# Stoitsov_Bostandzhieva.net
KiCad netlist of a schematic drawn in EAGLE
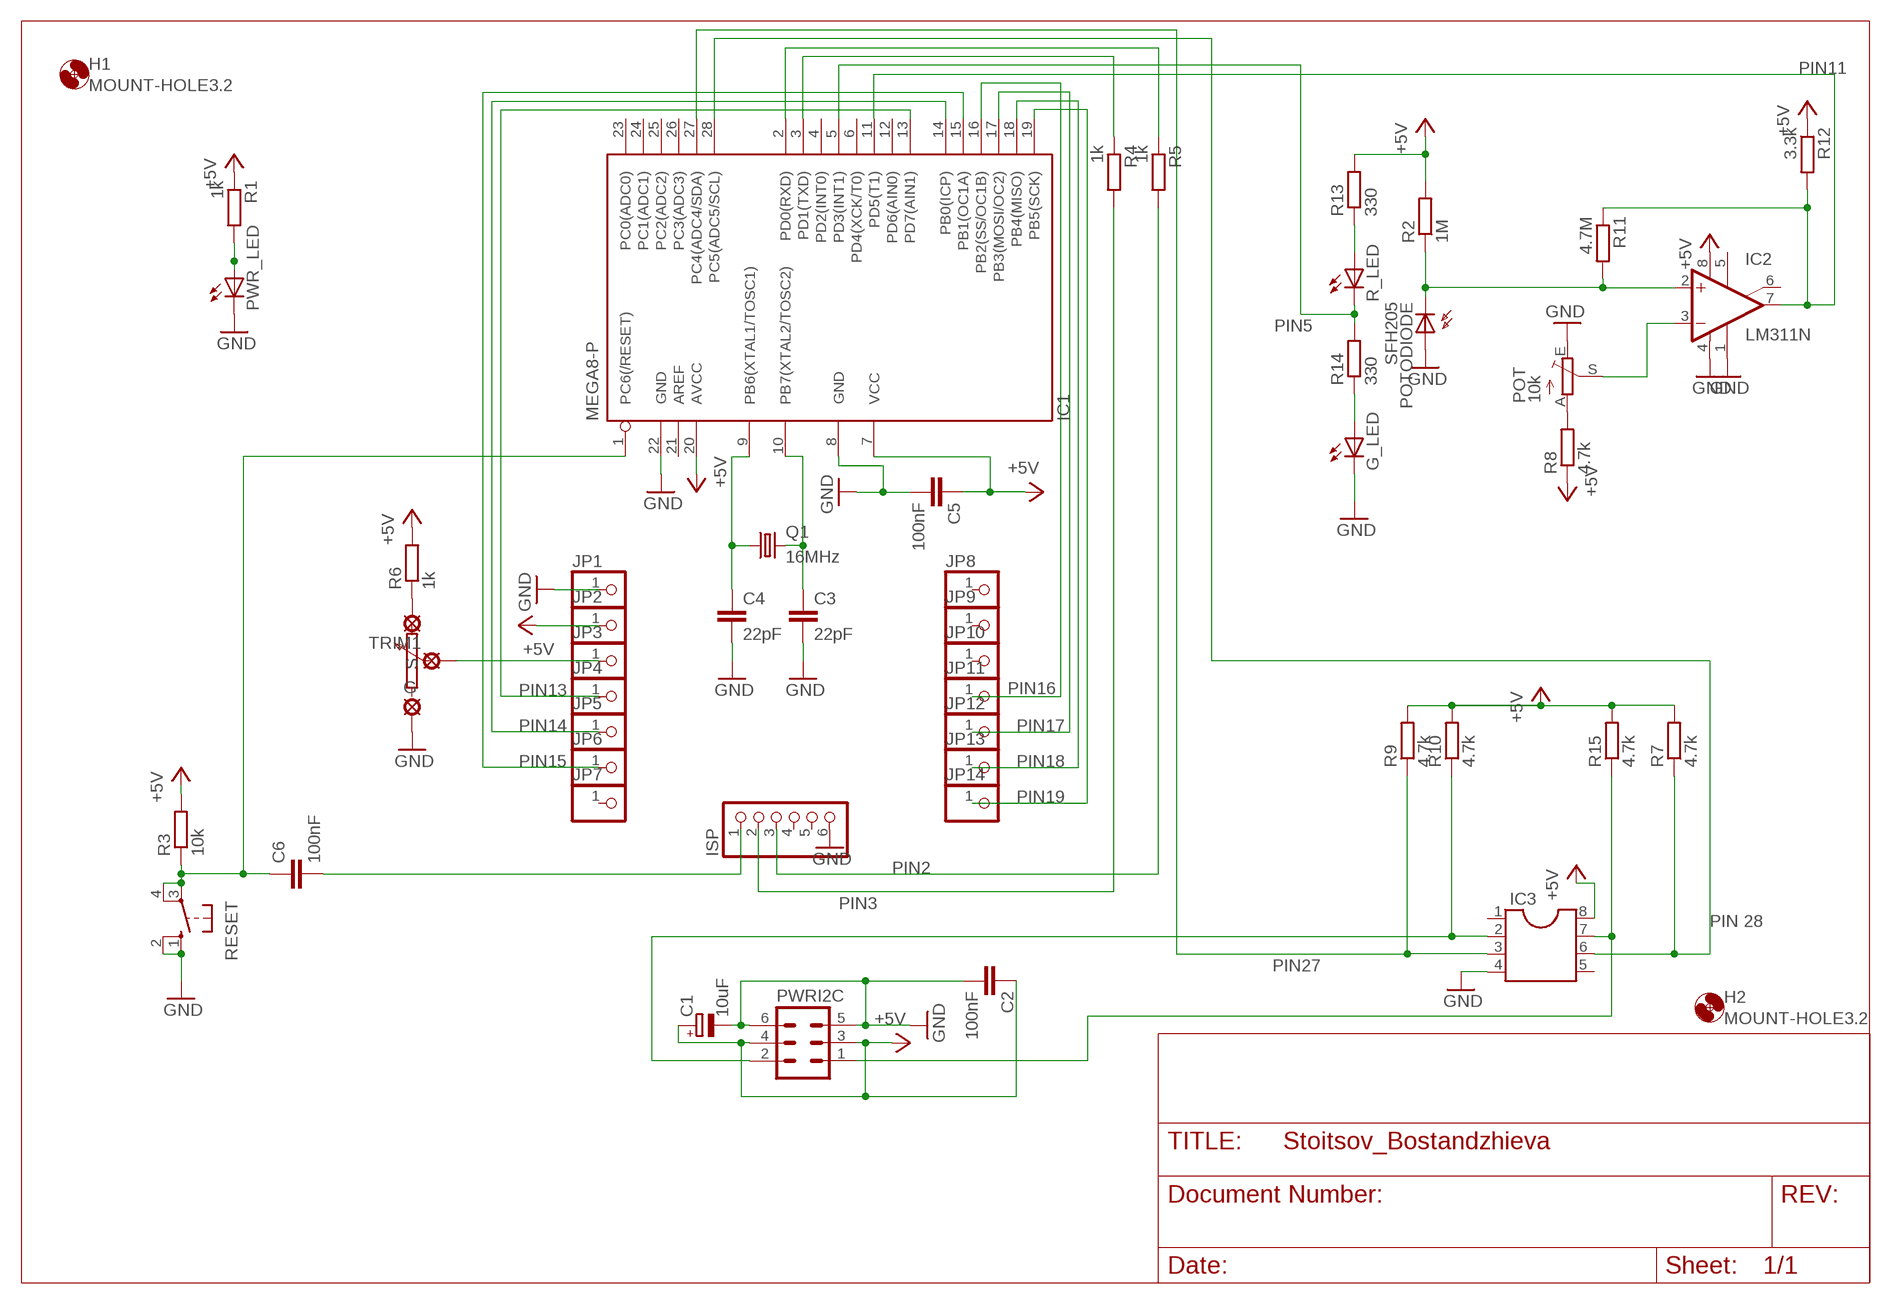
[diagram p0: schematic, sheet 1]

(export (version "E")
  (design (tool "Eeschema 10.0.6"))
  (components
    (comp (ref "C1")
      (value "10uF")
      (footprint "eagle-import:E5-6")
      (libsource (lib "eagle-import") (part "CPOL-EUE5-6"))
    )
    (comp (ref "C2")
      (value "100nF")
      (footprint "eagle-import:C5B2.5")
      (libsource (lib "eagle-import") (part "C5/2.5"))
    )
    (comp (ref "C3")
      (value "22pF")
      (footprint "eagle-import:C5B2.5")
      (libsource (lib "eagle-import") (part "C5/2.5"))
    )
    (comp (ref "C4")
      (value "22pF")
      (footprint "eagle-import:C5B2.5")
      (libsource (lib "eagle-import") (part "C5/2.5"))
    )
    (comp (ref "C5")
      (value "100nF")
      (footprint "eagle-import:C5B2.5")
      (libsource (lib "eagle-import") (part "C5/2.5"))
    )
    (comp (ref "C6")
      (value "100nF")
      (footprint "eagle-import:C5B2.5")
      (libsource (lib "eagle-import") (part "C5/2.5"))
    )
    (comp (ref "G")
      (value "LSP11")
      (footprint "eagle-import:LSP11")
      (libsource (lib "eagle-import") (part "LSP11"))
    )
    (comp (ref "G_LED")
      (value "LED3MM")
      (footprint "eagle-import:LED3MM")
      (libsource (lib "eagle-import") (part "LED3MM"))
    )
    (comp (ref "H1")
      (value "MOUNT-HOLE3.2")
      (footprint "eagle-import:3,2")
      (libsource (lib "eagle-import") (part "MOUNT-HOLE3.2"))
    )
    (comp (ref "H2")
      (value "MOUNT-HOLE3.2")
      (footprint "eagle-import:3,2")
      (libsource (lib "eagle-import") (part "MOUNT-HOLE3.2"))
    )
    (comp (ref "IC1")
      (value "MEGA8-P")
      (footprint "eagle-import:DIL28-3")
      (libsource (lib "eagle-import") (part "MEGA8-P"))
    )
    (comp (ref "IC2")
      (value "LM311N")
      (footprint "eagle-import:DIL08")
      (libsource (lib "eagle-import") (part "LM311N"))
    )
    (comp (ref "IC3")
      (value "DIL8S")
      (footprint "eagle-import:SOCKET-08")
      (libsource (lib "eagle-import") (part "DIL8S"))
    )
    (comp (ref "ISP")
      (value "PINHD-1X6/90")
      (footprint "eagle-import:1X06_90")
      (libsource (lib "eagle-import") (part "PINHD-1X6/90"))
    )
    (comp (ref "JP1")
      (value "PINHD-1X1")
      (footprint "eagle-import:1X01")
      (libsource (lib "eagle-import") (part "PINHD-1X1"))
    )
    (comp (ref "JP2")
      (value "PINHD-1X1")
      (footprint "eagle-import:1X01")
      (libsource (lib "eagle-import") (part "PINHD-1X1"))
    )
    (comp (ref "JP3")
      (value "PINHD-1X1")
      (footprint "eagle-import:1X01")
      (libsource (lib "eagle-import") (part "PINHD-1X1"))
    )
    (comp (ref "JP4")
      (value "PINHD-1X1")
      (footprint "eagle-import:1X01")
      (libsource (lib "eagle-import") (part "PINHD-1X1"))
    )
    (comp (ref "JP5")
      (value "PINHD-1X1")
      (footprint "eagle-import:1X01")
      (libsource (lib "eagle-import") (part "PINHD-1X1"))
    )
    (comp (ref "JP6")
      (value "PINHD-1X1")
      (footprint "eagle-import:1X01")
      (libsource (lib "eagle-import") (part "PINHD-1X1"))
    )
    (comp (ref "JP7")
      (value "PINHD-1X1")
      (footprint "eagle-import:1X01")
      (libsource (lib "eagle-import") (part "PINHD-1X1"))
    )
    (comp (ref "JP8")
      (value "PINHD-1X1")
      (footprint "eagle-import:1X01")
      (libsource (lib "eagle-import") (part "PINHD-1X1"))
    )
    (comp (ref "JP9")
      (value "PINHD-1X1")
      (footprint "eagle-import:1X01")
      (libsource (lib "eagle-import") (part "PINHD-1X1"))
    )
    (comp (ref "JP10")
      (value "PINHD-1X1")
      (footprint "eagle-import:1X01")
      (libsource (lib "eagle-import") (part "PINHD-1X1"))
    )
    (comp (ref "JP11")
      (value "PINHD-1X1")
      (footprint "eagle-import:1X01")
      (libsource (lib "eagle-import") (part "PINHD-1X1"))
    )
    (comp (ref "JP12")
      (value "PINHD-1X1")
      (footprint "eagle-import:1X01")
      (libsource (lib "eagle-import") (part "PINHD-1X1"))
    )
    (comp (ref "JP13")
      (value "PINHD-1X1")
      (footprint "eagle-import:1X01")
      (libsource (lib "eagle-import") (part "PINHD-1X1"))
    )
    (comp (ref "JP14")
      (value "PINHD-1X1")
      (footprint "eagle-import:1X01")
      (libsource (lib "eagle-import") (part "PINHD-1X1"))
    )
    (comp (ref "POT")
      (value "10k")
      (footprint "eagle-import:S64W")
      (libsource (lib "eagle-import") (part "TRIM_EU-S64W"))
    )
    (comp (ref "POTODIODE")
      (value "SFH205")
      (footprint "eagle-import:SFH205")
      (libsource (lib "eagle-import") (part "SFH205"))
    )
    (comp (ref "PWRI2C")
      (value "MA03-2")
      (footprint "eagle-import:MA03-2")
      (libsource (lib "eagle-import") (part "MA03-2"))
    )
    (comp (ref "PWR_LED")
      (value "LED3MM")
      (footprint "eagle-import:LED3MM")
      (libsource (lib "eagle-import") (part "LED3MM"))
    )
    (comp (ref "Q1")
      (value "16MHz")
      (footprint "eagle-import:HC18U-V")
      (libsource (lib "eagle-import") (part "CRYSTALHC18U-V"))
    )
    (comp (ref "R1")
      (value "1k")
      (footprint "eagle-import:0207_12")
      (libsource (lib "eagle-import") (part "R-EU_0207/12"))
    )
    (comp (ref "R2")
      (value "1M")
      (footprint "eagle-import:0207_12")
      (libsource (lib "eagle-import") (part "R-EU_0207/12"))
    )
    (comp (ref "R3")
      (value "10k")
      (footprint "eagle-import:0207_12")
      (libsource (lib "eagle-import") (part "R-EU_0207/12"))
    )
    (comp (ref "R4")
      (value "1k")
      (footprint "eagle-import:0207_12")
      (libsource (lib "eagle-import") (part "R-EU_0207/12"))
    )
    (comp (ref "R5")
      (value "1k")
      (footprint "eagle-import:0207_12")
      (libsource (lib "eagle-import") (part "R-EU_0207/12"))
    )
    (comp (ref "R6")
      (value "1k")
      (footprint "eagle-import:0207_12")
      (libsource (lib "eagle-import") (part "R-EU_0207/12"))
    )
    (comp (ref "R7")
      (value "4.7k")
      (footprint "eagle-import:0207_12")
      (libsource (lib "eagle-import") (part "R-EU_0207/12"))
    )
    (comp (ref "R8")
      (value "4.7k")
      (footprint "eagle-import:0207_12")
      (libsource (lib "eagle-import") (part "R-EU_0207/12"))
    )
    (comp (ref "R9")
      (value "4.7k")
      (footprint "eagle-import:0207_12")
      (libsource (lib "eagle-import") (part "R-EU_0207/12"))
    )
    (comp (ref "R10")
      (value "4.7k")
      (footprint "eagle-import:0207_12")
      (libsource (lib "eagle-import") (part "R-EU_0207/12"))
    )
    (comp (ref "R11")
      (value "4.7M")
      (footprint "eagle-import:0207_12")
      (libsource (lib "eagle-import") (part "R-EU_0207/12"))
    )
    (comp (ref "R12")
      (value "3.3k")
      (footprint "eagle-import:0207_12")
      (libsource (lib "eagle-import") (part "R-EU_0207/12"))
    )
    (comp (ref "R13")
      (value "330")
      (footprint "eagle-import:0207_12")
      (libsource (lib "eagle-import") (part "R-EU_0207/12"))
    )
    (comp (ref "R14")
      (value "330")
      (footprint "eagle-import:0207_12")
      (libsource (lib "eagle-import") (part "R-EU_0207/12"))
    )
    (comp (ref "R15")
      (value "4.7k")
      (footprint "eagle-import:0207_12")
      (libsource (lib "eagle-import") (part "R-EU_0207/12"))
    )
    (comp (ref "RESET")
      (value "10-XX")
      (footprint "eagle-import:B3F-10XX")
      (fields (field (name "MPN") "B3F-1000"))
      (libsource (lib "eagle-import") (part "10-XX"))
    )
    (comp (ref "R_LED")
      (value "LED3MM")
      (footprint "eagle-import:LED3MM")
      (libsource (lib "eagle-import") (part "LED3MM"))
    )
    (comp (ref "S")
      (value "LSP11")
      (footprint "eagle-import:LSP11")
      (libsource (lib "eagle-import") (part "LSP11"))
    )
    (comp (ref "TRIM1")
      (value "LSP11")
      (footprint "eagle-import:LSP11")
      (libsource (lib "eagle-import") (part "LSP11"))
    )
  )
  (nets
    (net (code "1") (name "+5V") (class "Default")
      (node (ref "C1") (pin "+") (pinfunction "+_+") (pintype "passive"))
      (node (ref "C2") (pin "1") (pinfunction "1_1") (pintype "passive"))
      (node (ref "C5") (pin "1") (pinfunction "1_1") (pintype "passive"))
      (node (ref "IC1") (pin "20") (pinfunction "AVCC_20") (pintype "power_in"))
      (node (ref "IC1") (pin "7") (pinfunction "VCC_7") (pintype "power_in"))
      (node (ref "IC2") (pin "8") (pinfunction "V+_8") (pintype "power_in"))
      (node (ref "IC3") (pin "8") (pinfunction "8_8") (pintype "passive"))
      (node (ref "JP2") (pin "1") (pinfunction "1_1") (pintype "passive"))
      (node (ref "PWRI2C") (pin "3") (pinfunction "3_3") (pintype "passive"))
      (node (ref "PWRI2C") (pin "4") (pinfunction "4_4") (pintype "passive"))
      (node (ref "R1") (pin "1") (pinfunction "1_1") (pintype "passive"))
      (node (ref "R10") (pin "2") (pinfunction "2_2") (pintype "passive"))
      (node (ref "R12") (pin "1") (pinfunction "1_1") (pintype "passive"))
      (node (ref "R13") (pin "2") (pinfunction "2_2") (pintype "passive"))
      (node (ref "R15") (pin "2") (pinfunction "2_2") (pintype "passive"))
      (node (ref "R2") (pin "2") (pinfunction "2_2") (pintype "passive"))
      (node (ref "R3") (pin "2") (pinfunction "2_2") (pintype "passive"))
      (node (ref "R6") (pin "2") (pinfunction "2_2") (pintype "passive"))
      (node (ref "R7") (pin "2") (pinfunction "2_2") (pintype "passive"))
      (node (ref "R8") (pin "1") (pinfunction "1_1") (pintype "passive"))
      (node (ref "R9") (pin "2") (pinfunction "2_2") (pintype "passive"))
    )
    (net (code "2") (name "GND") (class "Default")
      (node (ref "C1") (pin "-") (pinfunction "-_-") (pintype "passive"))
      (node (ref "C2") (pin "2") (pinfunction "2_2") (pintype "passive"))
      (node (ref "C3") (pin "2") (pinfunction "2_2") (pintype "passive"))
      (node (ref "C4") (pin "2") (pinfunction "2_2") (pintype "passive"))
      (node (ref "C5") (pin "2") (pinfunction "2_2") (pintype "passive"))
      (node (ref "G") (pin "MP") (pinfunction "MP_MP") (pintype "passive"))
      (node (ref "G_LED") (pin "K") (pinfunction "C_K") (pintype "passive"))
      (node (ref "IC1") (pin "22") (pinfunction "GND_22") (pintype "power_in"))
      (node (ref "IC1") (pin "8") (pinfunction "GND_8") (pintype "power_in"))
      (node (ref "IC2") (pin "1") (pinfunction "GND_1") (pintype "passive"))
      (node (ref "IC2") (pin "4") (pinfunction "V-_4") (pintype "power_in"))
      (node (ref "IC3") (pin "4") (pinfunction "4_4") (pintype "passive"))
      (node (ref "ISP") (pin "6") (pinfunction "6_6") (pintype "passive"))
      (node (ref "JP1") (pin "1") (pinfunction "1_1") (pintype "passive"))
      (node (ref "POT") (pin "E") (pinfunction "E_E") (pintype "passive"))
      (node (ref "POTODIODE") (pin "A") (pinfunction "A_A") (pintype "passive"))
      (node (ref "PWRI2C") (pin "5") (pinfunction "5_5") (pintype "passive"))
      (node (ref "PWRI2C") (pin "6") (pinfunction "6_6") (pintype "passive"))
      (node (ref "PWR_LED") (pin "K") (pinfunction "C_K") (pintype "passive"))
      (node (ref "RESET") (pin "1") (pinfunction "S_1") (pintype "passive"))
      (node (ref "RESET") (pin "2") (pinfunction "S1_2") (pintype "passive"))
    )
    (net (code "3") (name "Net-(C6-Pad2)") (class "Default")
      (node (ref "C6") (pin "2") (pinfunction "2_2") (pintype "passive"))
      (node (ref "ISP") (pin "1") (pinfunction "1_1") (pintype "passive"))
    )
    (net (code "4") (name "Net-(G_LED-PadA)") (class "Default")
      (node (ref "G_LED") (pin "A") (pinfunction "A_A") (pintype "passive"))
      (node (ref "R14") (pin "1") (pinfunction "1_1") (pintype "passive"))
    )
    (net (code "5") (name "Net-(IC1-PB0(ICP))") (class "Default")
      (node (ref "IC1") (pin "14") (pinfunction "PB0(ICP)_14") (pintype "bidirectional"))
      (node (ref "JP5") (pin "1") (pinfunction "1_1") (pintype "passive"))
    )
    (net (code "6") (name "Net-(IC1-PB1(OC1A))") (class "Default")
      (node (ref "IC1") (pin "15") (pinfunction "PB1(OC1A)_15") (pintype "bidirectional"))
      (node (ref "JP6") (pin "1") (pinfunction "1_1") (pintype "passive"))
    )
    (net (code "7") (name "Net-(IC1-PB2(SS{slash}OC1B))") (class "Default")
      (node (ref "IC1") (pin "16") (pinfunction "PB2(SS/OC1B)_16") (pintype "bidirectional"))
      (node (ref "JP11") (pin "1") (pinfunction "1_1") (pintype "passive"))
    )
    (net (code "8") (name "Net-(IC1-PB3(MOSI{slash}OC2))") (class "Default")
      (node (ref "IC1") (pin "17") (pinfunction "PB3(MOSI/OC2)_17") (pintype "bidirectional"))
      (node (ref "JP12") (pin "1") (pinfunction "1_1") (pintype "passive"))
    )
    (net (code "9") (name "Net-(IC1-PB4(MISO))") (class "Default")
      (node (ref "IC1") (pin "18") (pinfunction "PB4(MISO)_18") (pintype "bidirectional"))
      (node (ref "JP13") (pin "1") (pinfunction "1_1") (pintype "passive"))
    )
    (net (code "10") (name "Net-(IC1-PB5(SCK))") (class "Default")
      (node (ref "IC1") (pin "19") (pinfunction "PB5(SCK)_19") (pintype "bidirectional"))
      (node (ref "JP14") (pin "1") (pinfunction "1_1") (pintype "passive"))
    )
    (net (code "11") (name "Net-(IC1-PB6(XTAL1{slash}TOSC1))") (class "Default")
      (node (ref "C4") (pin "1") (pinfunction "1_1") (pintype "passive"))
      (node (ref "IC1") (pin "9") (pinfunction "PB6(XTAL1/TOSC1)_9") (pintype "bidirectional"))
      (node (ref "Q1") (pin "1") (pinfunction "1_1") (pintype "passive"))
    )
    (net (code "12") (name "Net-(IC1-PB7(XTAL2{slash}TOSC2))") (class "Default")
      (node (ref "C3") (pin "1") (pinfunction "1_1") (pintype "passive"))
      (node (ref "IC1") (pin "10") (pinfunction "PB7(XTAL2/TOSC2)_10") (pintype "bidirectional"))
      (node (ref "Q1") (pin "2") (pinfunction "2_2") (pintype "passive"))
    )
    (net (code "13") (name "Net-(IC1-PC4(ADC4{slash}SDA))") (class "Default")
      (node (ref "IC1") (pin "27") (pinfunction "PC4(ADC4/SDA)_27") (pintype "bidirectional"))
      (node (ref "IC3") (pin "3") (pinfunction "3_3") (pintype "passive"))
      (node (ref "R9") (pin "1") (pinfunction "1_1") (pintype "passive"))
    )
    (net (code "14") (name "Net-(IC1-PC5(ADC5{slash}SCL))") (class "Default")
      (node (ref "IC1") (pin "28") (pinfunction "PC5(ADC5/SCL)_28") (pintype "bidirectional"))
      (node (ref "IC3") (pin "6") (pinfunction "6_6") (pintype "passive"))
      (node (ref "R7") (pin "1") (pinfunction "1_1") (pintype "passive"))
    )
    (net (code "15") (name "Net-(IC1-PC6({slash}RESET))") (class "Default")
      (node (ref "C6") (pin "1") (pinfunction "1_1") (pintype "passive"))
      (node (ref "IC1") (pin "1") (pinfunction "PC6(/RESET)_1") (pintype "bidirectional"))
      (node (ref "R3") (pin "1") (pinfunction "1_1") (pintype "passive"))
      (node (ref "RESET") (pin "3") (pinfunction "P_3") (pintype "passive"))
      (node (ref "RESET") (pin "4") (pinfunction "P1_4") (pintype "passive"))
    )
    (net (code "16") (name "Net-(IC1-PD0(RXD))") (class "Default")
      (node (ref "IC1") (pin "2") (pinfunction "PD0(RXD)_2") (pintype "bidirectional"))
      (node (ref "R5") (pin "1") (pinfunction "1_1") (pintype "passive"))
    )
    (net (code "17") (name "Net-(IC1-PD1(TXD))") (class "Default")
      (node (ref "IC1") (pin "3") (pinfunction "PD1(TXD)_3") (pintype "bidirectional"))
      (node (ref "R4") (pin "1") (pinfunction "1_1") (pintype "passive"))
    )
    (net (code "18") (name "Net-(IC1-PD3(INT1))") (class "Default")
      (node (ref "IC1") (pin "5") (pinfunction "PD3(INT1)_5") (pintype "bidirectional"))
      (node (ref "R14") (pin "2") (pinfunction "2_2") (pintype "passive"))
      (node (ref "R_LED") (pin "K") (pinfunction "C_K") (pintype "passive"))
    )
    (net (code "19") (name "Net-(IC1-PD5(T1))") (class "Default")
      (node (ref "IC1") (pin "11") (pinfunction "PD5(T1)_11") (pintype "bidirectional"))
      (node (ref "IC2") (pin "7") (pinfunction "OUT_7") (pintype "output"))
      (node (ref "R11") (pin "1") (pinfunction "1_1") (pintype "passive"))
      (node (ref "R12") (pin "2") (pinfunction "2_2") (pintype "passive"))
    )
    (net (code "20") (name "Net-(IC1-PD7(AIN1))") (class "Default")
      (node (ref "IC1") (pin "13") (pinfunction "PD7(AIN1)_13") (pintype "bidirectional"))
      (node (ref "JP4") (pin "1") (pinfunction "1_1") (pintype "passive"))
    )
    (net (code "21") (name "Net-(IC2-+IN)") (class "Default")
      (node (ref "IC2") (pin "2") (pinfunction "+IN_2") (pintype "input"))
      (node (ref "POTODIODE") (pin "K") (pinfunction "C_K") (pintype "passive"))
      (node (ref "R11") (pin "2") (pinfunction "2_2") (pintype "passive"))
      (node (ref "R2") (pin "1") (pinfunction "1_1") (pintype "passive"))
    )
    (net (code "22") (name "Net-(IC2--IN)") (class "Default")
      (node (ref "IC2") (pin "3") (pinfunction "-IN_3") (pintype "input"))
      (node (ref "POT") (pin "S") (pinfunction "S_S") (pintype "passive"))
    )
    (net (code "23") (name "Net-(IC3-Pad2)") (class "Default")
      (node (ref "IC3") (pin "2") (pinfunction "2_2") (pintype "passive"))
      (node (ref "PWRI2C") (pin "2") (pinfunction "2_2") (pintype "passive"))
      (node (ref "R10") (pin "1") (pinfunction "1_1") (pintype "passive"))
    )
    (net (code "24") (name "Net-(IC3-Pad7)") (class "Default")
      (node (ref "IC3") (pin "7") (pinfunction "7_7") (pintype "passive"))
      (node (ref "PWRI2C") (pin "1") (pinfunction "1_1") (pintype "passive"))
      (node (ref "R15") (pin "1") (pinfunction "1_1") (pintype "passive"))
    )
    (net (code "25") (name "Net-(ISP-Pad2)") (class "Default")
      (node (ref "ISP") (pin "2") (pinfunction "2_2") (pintype "passive"))
      (node (ref "R4") (pin "2") (pinfunction "2_2") (pintype "passive"))
    )
    (net (code "26") (name "Net-(ISP-Pad3)") (class "Default")
      (node (ref "ISP") (pin "3") (pinfunction "3_3") (pintype "passive"))
      (node (ref "R5") (pin "2") (pinfunction "2_2") (pintype "passive"))
    )
    (net (code "27") (name "Net-(JP3-Pad1)") (class "Default")
      (node (ref "JP3") (pin "1") (pinfunction "1_1") (pintype "passive"))
      (node (ref "S") (pin "MP") (pinfunction "MP_MP") (pintype "passive"))
    )
    (net (code "28") (name "Net-(POT-PadA)") (class "Default")
      (node (ref "POT") (pin "A") (pinfunction "A_A") (pintype "passive"))
      (node (ref "R8") (pin "2") (pinfunction "2_2") (pintype "passive"))
    )
    (net (code "29") (name "Net-(PWR_LED-PadA)") (class "Default")
      (node (ref "PWR_LED") (pin "A") (pinfunction "A_A") (pintype "passive"))
      (node (ref "R1") (pin "2") (pinfunction "2_2") (pintype "passive"))
    )
    (net (code "30") (name "Net-(R6-Pad1)") (class "Default")
      (node (ref "R6") (pin "1") (pinfunction "1_1") (pintype "passive"))
      (node (ref "TRIM1") (pin "MP") (pinfunction "MP_MP") (pintype "passive"))
    )
    (net (code "31") (name "Net-(R13-Pad1)") (class "Default")
      (node (ref "R13") (pin "1") (pinfunction "1_1") (pintype "passive"))
      (node (ref "R_LED") (pin "A") (pinfunction "A_A") (pintype "passive"))
    )
    (net (code "32") (name "unconnected-(IC1-AREF-Pad21)") (class "Default")
      (node (ref "IC1") (pin "21") (pinfunction "AREF_21") (pintype "passive"))
    )
    (net (code "33") (name "unconnected-(IC1-PC0(ADC0)-Pad23)") (class "Default")
      (node (ref "IC1") (pin "23") (pinfunction "PC0(ADC0)_23") (pintype "bidirectional"))
    )
    (net (code "34") (name "unconnected-(IC1-PC1(ADC1)-Pad24)") (class "Default")
      (node (ref "IC1") (pin "24") (pinfunction "PC1(ADC1)_24") (pintype "bidirectional"))
    )
    (net (code "35") (name "unconnected-(IC1-PC2(ADC2)-Pad25)") (class "Default")
      (node (ref "IC1") (pin "25") (pinfunction "PC2(ADC2)_25") (pintype "bidirectional"))
    )
    (net (code "36") (name "unconnected-(IC1-PC3(ADC3)-Pad26)") (class "Default")
      (node (ref "IC1") (pin "26") (pinfunction "PC3(ADC3)_26") (pintype "bidirectional"))
    )
    (net (code "37") (name "unconnected-(IC1-PD2(INT0)-Pad4)") (class "Default")
      (node (ref "IC1") (pin "4") (pinfunction "PD2(INT0)_4") (pintype "bidirectional"))
    )
    (net (code "38") (name "unconnected-(IC1-PD4(XCK{slash}T0)-Pad6)") (class "Default")
      (node (ref "IC1") (pin "6") (pinfunction "PD4(XCK/T0)_6") (pintype "bidirectional"))
    )
    (net (code "39") (name "unconnected-(IC1-PD6(AIN0)-Pad12)") (class "Default")
      (node (ref "IC1") (pin "12") (pinfunction "PD6(AIN0)_12") (pintype "bidirectional"))
    )
    (net (code "40") (name "unconnected-(IC2-ON-Pad5)") (class "Default")
      (node (ref "IC2") (pin "5") (pinfunction "ON_5") (pintype "passive"))
    )
    (net (code "41") (name "unconnected-(IC2-ON{slash}STR-Pad6)") (class "Default")
      (node (ref "IC2") (pin "6") (pinfunction "ON/STR_6") (pintype "passive"))
    )
    (net (code "42") (name "unconnected-(IC3-Pad1)") (class "Default")
      (node (ref "IC3") (pin "1") (pinfunction "1_1") (pintype "passive"))
    )
    (net (code "43") (name "unconnected-(IC3-Pad5)") (class "Default")
      (node (ref "IC3") (pin "5") (pinfunction "5_5") (pintype "passive"))
    )
    (net (code "44") (name "unconnected-(ISP-Pad4)") (class "Default")
      (node (ref "ISP") (pin "4") (pinfunction "4_4") (pintype "passive"))
    )
    (net (code "45") (name "unconnected-(ISP-Pad5)") (class "Default")
      (node (ref "ISP") (pin "5") (pinfunction "5_5") (pintype "passive"))
    )
    (net (code "46") (name "unconnected-(JP7-Pad1)") (class "Default")
      (node (ref "JP7") (pin "1") (pinfunction "1_1") (pintype "passive"))
    )
    (net (code "47") (name "unconnected-(JP8-Pad1)") (class "Default")
      (node (ref "JP8") (pin "1") (pinfunction "1_1") (pintype "passive"))
    )
    (net (code "48") (name "unconnected-(JP9-Pad1)") (class "Default")
      (node (ref "JP9") (pin "1") (pinfunction "1_1") (pintype "passive"))
    )
    (net (code "49") (name "unconnected-(JP10-Pad1)") (class "Default")
      (node (ref "JP10") (pin "1") (pinfunction "1_1") (pintype "passive"))
    )
  )
)
